# NEH.net
KiCad netlist of a schematic drawn in Altium Designer
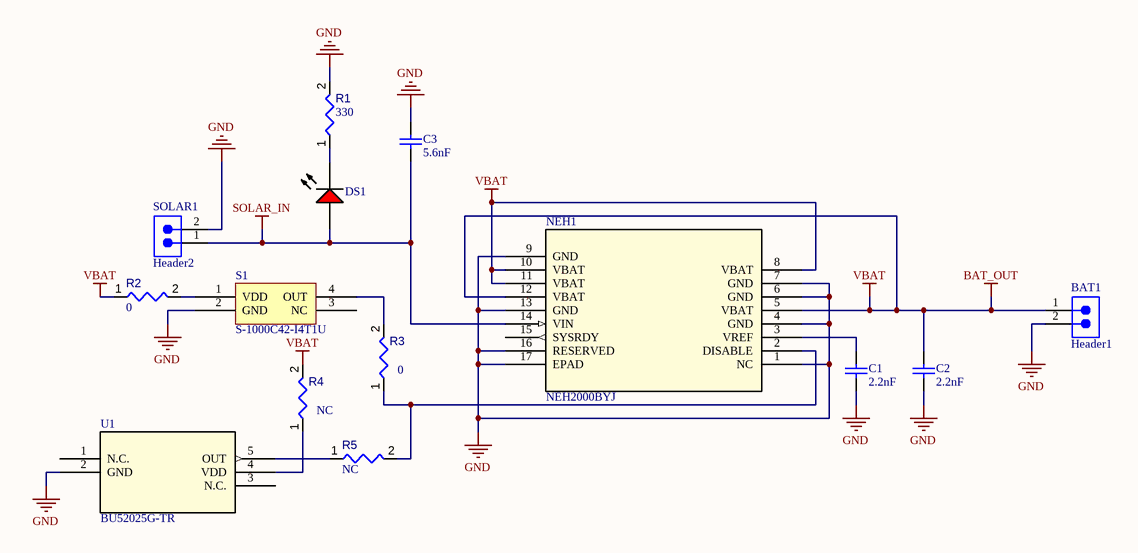
[diagram p0: NEH.SchDoc]

(export (version "E")
  (design (tool "Eeschema 10.0.6"))
  (components
    (comp (ref "BAT1")
      (value "Header1")
      (footprint "61300211121")
      (libsource (lib "21520293 21520293") (part "Header_Male_1R_02P"))
    )
    (comp (ref "C1")
      (value "2.2nF")
      (footprint "CAPC0603X33X15LL03T05")
      (fields (field (name "Comment") "0201YD222KAT2A"))
      (libsource (lib "21520293 21520293") (part "CAP"))
    )
    (comp (ref "C2")
      (value "2.2nF")
      (footprint "CAPC0603X33X15LL03T05")
      (fields (field (name "Comment") "0201YD222KAT2A"))
      (libsource (lib "21520293 21520293") (part "CAP"))
    )
    (comp (ref "C3")
      (value "5.6nF")
      (footprint "rlc_402_smd_small")
      (description "Capacitor SMD")
      (fields (field (name "Comment") "Cap") (field (name "PUBLISHER") "Altium Limited"))
      (libsource (lib "SX126xMB2xAS_e588v01a") (part "Cap"))
    )
    (comp (ref "DS1")
      (value "19-217/R6C-AL1M2VY/3T")
      (footprint "EVRL-0603-2_V")
      (description "Chip LED, Red, 5 V, 25 mA, -40 to 85 degC, 2-Pin SMD (0603), RoHS, Tape and Reel")
      (fields (field (name "MANUFACTURER") "Everlight Electronics"))
      (libsource (lib "21520293 21520293") (part "LED-RED-AK-2"))
    )
    (comp (ref "NEH1")
      (value "NEH2000BYJ")
      (footprint "HWQFN16_SOT8076-1_NEX")
      (description "No Description Available")
      (fields (field (name "COPYRIGHT") "Copyright (C) 2023 Ultra Librarian. All rights reserved."))
      (libsource (lib "NEH2000BYJ") (part "NEH2000BYJ"))
    )
    (comp (ref "R1")
      (value "330")
      (footprint "RESC0402(1005)_L")
      (description "330R 0.063W 5% 0402 (1005 Metric)  SMD")
      (fields (field (name "TOLERANCE") "5%") (field (name "POWER") "63mW"))
      (libsource (lib "21520293 21520293") (part "330R2J"))
    )
    (comp (ref "R2")
      (value "0")
      (footprint "RESC0603(1608)_L")
      (description "Jumper 0603")
      (libsource (lib "21520293 21520293") (part "RES-2"))
    )
    (comp (ref "R3")
      (value "0")
      (footprint "RESC0603(1608)_L")
      (description "Jumper 0603")
      (libsource (lib "21520293 21520293") (part "RES-2"))
    )
    (comp (ref "R4")
      (value "NC")
      (footprint "RESC0603(1608)_L")
      (description "Jumper 0603")
      (libsource (lib "21520293 21520293") (part "RES-2"))
    )
    (comp (ref "R5")
      (value "NC")
      (footprint "RESC0603(1608)_L")
      (description "Jumper 0603")
      (libsource (lib "21520293 21520293") (part "RES-2"))
    )
    (comp (ref "S1")
      (value "S-1000C42-I4T1U")
      (footprint "SON65P140X48_HS-5N")
      (description "Voltage Detector")
      (libsource (lib "21520293 21520293") (part "S-1000C42-I4T1U-Symbol-1"))
    )
    (comp (ref "SOLAR1")
      (value "Header2")
      (footprint "61300211121")
      (libsource (lib "21520293 21520293") (part "Header_Male_1R_02P"))
    )
    (comp (ref "U1")
      (value "BU52025G-TR")
      (footprint "BU52025G-TR:SSOP5_ROM")
      (description "No Description Available")
      (libsource (lib "BU52025G-TR") (part "BU52025G-TR"))
    )
  )
  (nets
    (net (code "1") (name "BAT_OUT") (class "Default")
      (node (ref "BAT1") (pin "1") (pinfunction "1_1") (pintype "passive"))
      (node (ref "C2") (pin "2") (pinfunction "2_2") (pintype "passive"))
      (node (ref "NEH1") (pin "10") (pinfunction "VBAT_10") (pintype "power_in"))
      (node (ref "NEH1") (pin "11") (pinfunction "VBAT_11") (pintype "power_in"))
      (node (ref "NEH1") (pin "12") (pinfunction "VBAT_12") (pintype "power_in"))
      (node (ref "NEH1") (pin "5") (pinfunction "VBAT_5") (pintype "power_in"))
      (node (ref "NEH1") (pin "8") (pinfunction "VBAT_8") (pintype "power_in"))
      (node (ref "R2") (pin "1") (pinfunction "1_1") (pintype "passive"))
      (node (ref "R4") (pin "2") (pinfunction "2_2") (pintype "passive"))
    )
    (net (code "2") (name "GND") (class "Default")
      (node (ref "BAT1") (pin "2") (pinfunction "2_2") (pintype "passive"))
      (node (ref "C1") (pin "1") (pinfunction "1_1") (pintype "passive"))
      (node (ref "C2") (pin "1") (pinfunction "1_1") (pintype "passive"))
      (node (ref "C3") (pin "2") (pinfunction "2_2") (pintype "passive"))
      (node (ref "NEH1") (pin "1") (pinfunction "NC_1") (pintype "passive"))
      (node (ref "NEH1") (pin "13") (pinfunction "GND_13") (pintype "power_in"))
      (node (ref "NEH1") (pin "16") (pinfunction "RESERVED_16") (pintype "passive"))
      (node (ref "NEH1") (pin "17") (pinfunction "EPAD_17") (pintype "power_in"))
      (node (ref "NEH1") (pin "4") (pinfunction "GND_4") (pintype "power_in"))
      (node (ref "NEH1") (pin "6") (pinfunction "GND_6") (pintype "power_in"))
      (node (ref "NEH1") (pin "7") (pinfunction "GND_7") (pintype "power_in"))
      (node (ref "NEH1") (pin "9") (pinfunction "GND_9") (pintype "power_in"))
      (node (ref "R1") (pin "2") (pinfunction "2_2") (pintype "passive"))
      (node (ref "S1") (pin "2") (pinfunction "GND_2") (pintype "passive"))
      (node (ref "SOLAR1") (pin "2") (pinfunction "2_2") (pintype "passive"))
      (node (ref "U1") (pin "2") (pinfunction "GND_2") (pintype "power_in"))
    )
    (net (code "3") (name "Net-(DS1-K)") (class "Default")
      (node (ref "DS1") (pin "2") (pinfunction "K_2") (pintype "passive"))
      (node (ref "R1") (pin "1") (pinfunction "1_1") (pintype "passive"))
    )
    (net (code "4") (name "Net-(NEH1-DISABLE)") (class "Default")
      (node (ref "NEH1") (pin "2") (pinfunction "DISABLE_2") (pintype "passive"))
      (node (ref "R3") (pin "1") (pinfunction "1_1") (pintype "passive"))
      (node (ref "R5") (pin "2") (pinfunction "2_2") (pintype "passive"))
    )
    (net (code "5") (name "Net-(NEH1-VREF)") (class "Default")
      (node (ref "C1") (pin "2") (pinfunction "2_2") (pintype "passive"))
      (node (ref "NEH1") (pin "3") (pinfunction "VREF_3") (pintype "power_in"))
    )
    (net (code "6") (name "Net-(S1-OUT)") (class "Default")
      (node (ref "R3") (pin "2") (pinfunction "2_2") (pintype "passive"))
      (node (ref "S1") (pin "4") (pinfunction "OUT_4") (pintype "passive"))
    )
    (net (code "7") (name "Net-(S1-VDD)") (class "Default")
      (node (ref "R2") (pin "2") (pinfunction "2_2") (pintype "passive"))
      (node (ref "S1") (pin "1") (pinfunction "VDD_1") (pintype "passive"))
    )
    (net (code "8") (name "Net-(U1-OUT)") (class "Default")
      (node (ref "R5") (pin "1") (pinfunction "1_1") (pintype "passive"))
      (node (ref "U1") (pin "5") (pinfunction "OUT_5") (pintype "output"))
    )
    (net (code "9") (name "Net-(U1-VDD)") (class "Default")
      (node (ref "R4") (pin "1") (pinfunction "1_1") (pintype "passive"))
      (node (ref "U1") (pin "4") (pinfunction "VDD_4") (pintype "power_in"))
    )
    (net (code "10") (name "SOLAR_IN") (class "Default")
      (node (ref "C3") (pin "1") (pinfunction "1_1") (pintype "passive"))
      (node (ref "DS1") (pin "1") (pinfunction "A_1") (pintype "passive"))
      (node (ref "NEH1") (pin "14") (pinfunction "VIN_14") (pintype "input"))
      (node (ref "SOLAR1") (pin "1") (pinfunction "1_1") (pintype "passive"))
    )
    (net (code "11") (name "unconnected-(NEH1-SYSRDY-Pad15)") (class "Default")
      (node (ref "NEH1") (pin "15") (pinfunction "SYSRDY_15") (pintype "output"))
    )
    (net (code "12") (name "unconnected-(S1-NC-Pad3)") (class "Default")
      (node (ref "S1") (pin "3") (pinfunction "NC_3") (pintype "tri_state"))
    )
    (net (code "13") (name "unconnected-(U1-N.C.-Pad1)") (class "Default")
      (node (ref "U1") (pin "1") (pinfunction "N.C._1") (pintype "passive"))
    )
    (net (code "14") (name "unconnected-(U1-N.C.-Pad3)") (class "Default")
      (node (ref "U1") (pin "3") (pinfunction "N.C._3") (pintype "passive"))
    )
  )
)
